# VermogensPrint.net
KiCad netlist of a schematic drawn in Altium Designer
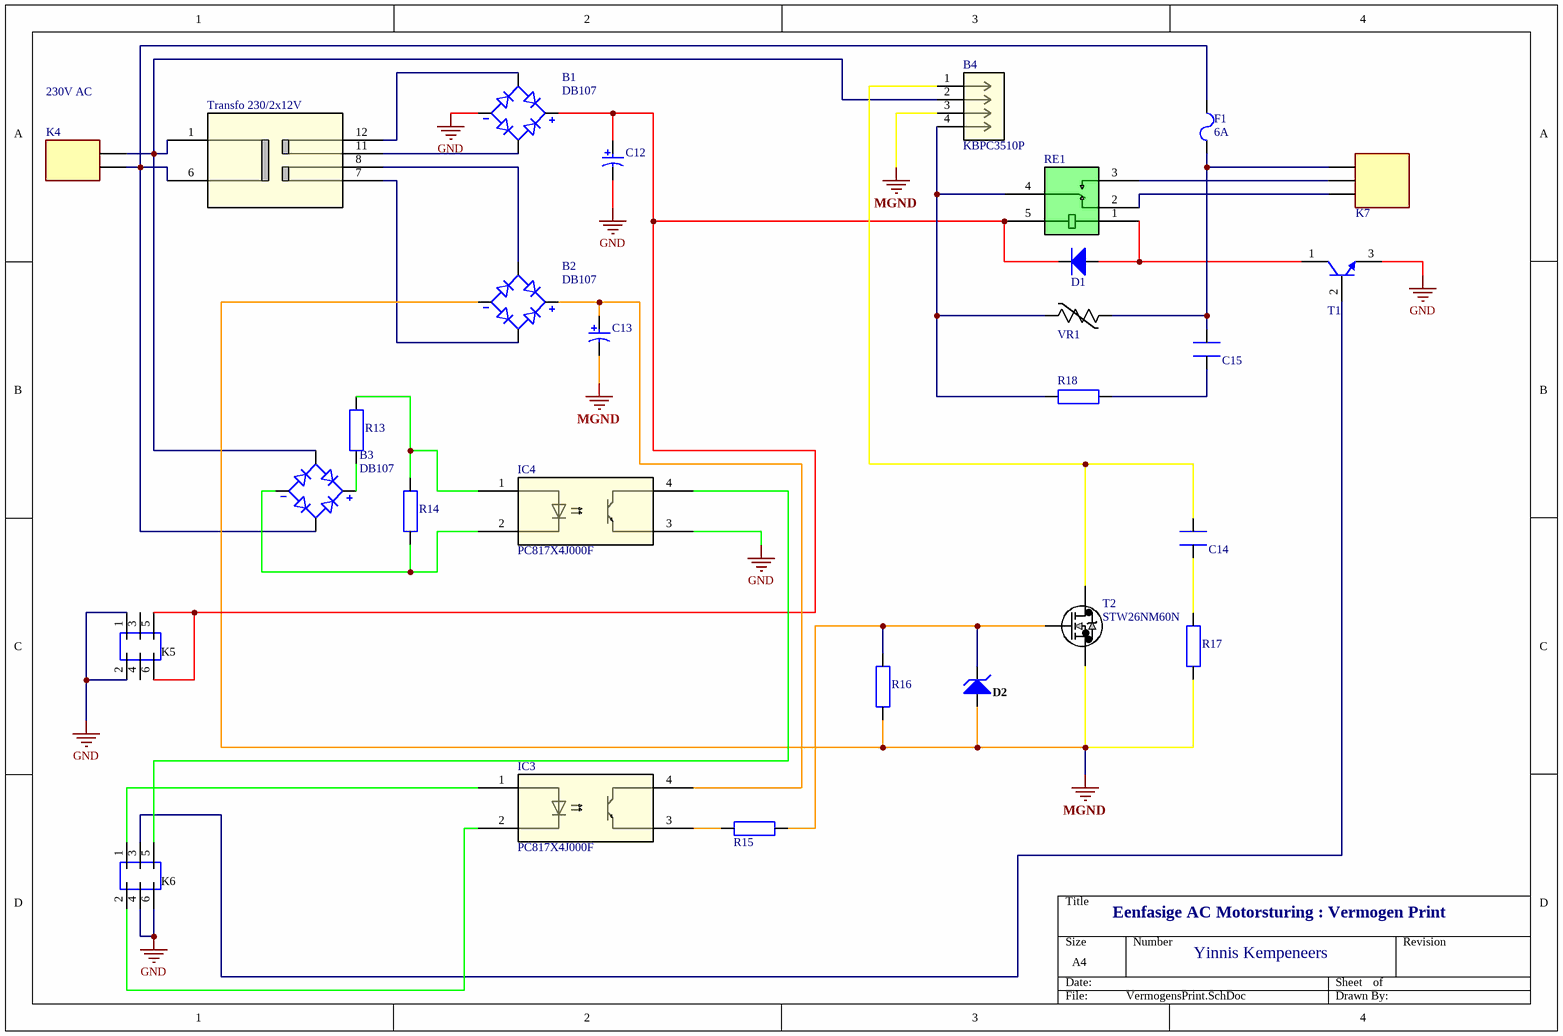
[diagram p0: VermogensPrint.SchDoc]

(export (version "E")
  (design (tool "Eeschema 10.0.6"))
  (components
    (comp (ref "B1")
      (value "DB107")
      (footprint "DB107")
      (libsource (lib "Schlib_Motorvermogen") (part "DB107"))
    )
    (comp (ref "B2")
      (value "DB107")
      (footprint "DB107")
      (libsource (lib "Schlib_Motorvermogen") (part "DB107"))
    )
    (comp (ref "B3")
      (value "DB107")
      (footprint "DB107")
      (libsource (lib "Schlib_Motorvermogen") (part "DB107"))
    )
    (comp (ref "B4")
      (value "KBPC3510P")
      (footprint "KBPC3510")
      (description "No Description Available")
      (libsource (lib "Schlib_Motorvermogen") (part "KBPC3510P"))
    )
    (comp (ref "C12")
      (value "470µF")
      (footprint "Capacitor")
      (description "Capacitor 470µF 50V")
      (libsource (lib "Schlib_Motorvermogen") (part "470µF"))
    )
    (comp (ref "C13")
      (value "470µF")
      (footprint "Capacitor")
      (description "Capacitor 470µF 50V")
      (libsource (lib "Schlib_Motorvermogen") (part "470µF"))
    )
    (comp (ref "C14")
      (value "Capacitor 0.22µF 630V")
      (footprint "0.22µF")
      (libsource (lib "Schlib_Motorvermogen") (part "Capacitor 0.22µF 630V"))
    )
    (comp (ref "C15")
      (value "0.22µF")
      (footprint "0.22µF")
      (description "Capacitor 0.22µF 630V")
      (libsource (lib "Schlib_Motorvermogen") (part "Capacitor 0.22µF 630V"))
    )
    (comp (ref "D1")
      (value "1N4007-T")
      (footprint "1N4007-T")
      (description "1.0 A Rectifier, 8 pF, 1000 V, -65 to 150 degC, 2-Pin DO-41 Plastic, RoHS, Tape and Reel")
      (fields (field (name "MANUFACTURER") "Diodes Inc"))
      (libsource (lib "Schlib_Motorvermogen") (part "1N4007-T"))
    )
    (comp (ref "D2")
      (value "1N4742A")
      (footprint "1N4742A")
      (description "Zener Diode, 12V, 1W, 5%, -65 to 200 degC, 2-Pin DO-41, Body 2.72 x 5.2 mm, RoHS")
      (fields (field (name "TOLERANCE") "5%") (field (name "MANUFACTURER") "Fairchild Semiconductor"))
      (libsource (lib "Schlib_Motorvermogen") (part "1N4742A"))
    )
    (comp (ref "F1")
      (value "6A")
      (footprint "FUSE")
      (description "No Description Available")
      (libsource (lib "Schlib_Motorvermogen") (part "Fuse"))
    )
    (comp (ref "IC3")
      (value "PC817X4J000F")
      (footprint "PC817X4J000F")
      (description "OptoCoupler")
      (libsource (lib "Schlib_Motorvermogen") (part "PC817X4J000F"))
    )
    (comp (ref "IC4")
      (value "PC817X4J000F")
      (footprint "PC817X4J000F")
      (description "OptoCoupler")
      (libsource (lib "Schlib_Motorvermogen") (part "PC817X4J000F"))
    )
    (comp (ref "K4")
      (value "~")
      (footprint "2-Polige Connector")
      (description "2~24 Poles, Screw Type, Horizontal, 7.62 Pitch, 26~10 (AWG), Terminal Block Connector")
      (fields (field (name "MP") "TB005-762-02BE") (field (name "MF") "CUI Devices"))
      (libsource (lib "Schlib_Motorvermogen") (part "2-Polige Connector"))
    )
    (comp (ref "K5")
      (value "TSW-103-08-L-D")
      (footprint "Pin3x2")
      (description "Male Header, Pitch 2.54 mm, 2 x 3 Position,  8.9 x 15.22 x 11.95 mm")
      (fields (field (name "MANUFACTURER") "Samtec"))
      (libsource (lib "Schlib_Motorvermogen") (part "Connector3x2"))
    )
    (comp (ref "K6")
      (value "TSW-103-08-L-D")
      (footprint "Pin3x2")
      (description "Male Header, Pitch 2.54 mm, 2 x 3 Position,  8.9 x 15.22 x 11.95 mm")
      (fields (field (name "MANUFACTURER") "Samtec"))
      (libsource (lib "Schlib_Motorvermogen") (part "Connector3x2"))
    )
    (comp (ref "K7")
      (value "3-Polige Connetor")
      (footprint "3-Polige Connector")
      (fields (field (name "MP") "TB005-762-03BE"))
      (libsource (lib "Schlib_Motorvermogen") (part "3-Polige Connetor"))
    )
    (comp (ref "R13")
      (value "47K 3W")
      (footprint "47K 3W")
      (libsource (lib "Schlib_Motorvermogen") (part "47K 3W"))
    )
    (comp (ref "R14")
      (value "10K 2W")
      (footprint "Resistor")
      (libsource (lib "Schlib_Motorvermogen") (part "Resistor 250mW"))
    )
    (comp (ref "R15")
      (value "1K")
      (footprint "Resistor")
      (libsource (lib "Schlib_Motorvermogen") (part "Resistor 250mW"))
    )
    (comp (ref "R16")
      (value "10K")
      (footprint "Resistor")
      (libsource (lib "Schlib_Motorvermogen") (part "Resistor 250mW"))
    )
    (comp (ref "R17")
      (value "2K2 2W")
      (footprint "2K2 2W")
      (libsource (lib "Schlib_Motorvermogen") (part "2K2 2W"))
    )
    (comp (ref "R18")
      (value "560E 5W")
      (footprint "560Ohm 5W")
      (description "Resistor, 560 Ohm, ± 5%, 5 W, Axial Leaded, Wirewound, General Purpose")
      (fields (field (name "TOLERANCE") "5%"))
      (libsource (lib "Schlib_Motorvermogen") (part "560ohm5W"))
    )
    (comp (ref "RE1")
      (value "G2R-14 DC12")
      (footprint "RELAY_G2R-14_OMR")
      (description "No Description Available")
      (libsource (lib "Schlib_Motorvermogen") (part "G2R-14 DC12"))
    )
    (comp (ref "T1")
      (value "BC547B")
      (footprint "Transistor")
      (description "Amplifier Transistor, NPN Silicon, 3-Pin TO-92, Bulk Box")
      (fields (field (name "MANUFACTURER") "On Semiconductor"))
      (libsource (lib "Schlib_Motorvermogen") (part "BC547B"))
    )
    (comp (ref "T2")
      (value "STW26NM60N")
      (footprint "TO-247_STM")
      (description "No Description Available")
      (libsource (lib "Schlib_Motorvermogen") (part "STW26NM60N"))
    )
    (comp (ref "Transfo 230/2x12V")
      (value "T1")
      (footprint "T1")
      (description "No Description Available")
      (libsource (lib "Schlib_Motorvermogen") (part "T1"))
    )
    (comp (ref "VR1")
      (value "V25S275P")
      (footprint "VRES_V25S385P_LTF")
      (description "No Description Available")
      (libsource (lib "Schlib_Motorvermogen") (part "V25S385P"))
    )
  )
  (nets
    (net (code "1") (name "GND") (class "Default")
      (node (ref "B1") (pin "2") (pinfunction "NEG_2") (pintype "passive"))
      (node (ref "C12") (pin "2") (pinfunction "2_2") (pintype "passive"))
      (node (ref "IC4") (pin "3") (pinfunction "3_3") (pintype "passive"))
      (node (ref "K5") (pin "1") (pinfunction "1_1") (pintype "passive"))
      (node (ref "K5") (pin "2") (pinfunction "2_2") (pintype "passive"))
      (node (ref "K6") (pin "4") (pinfunction "4_4") (pintype "passive"))
      (node (ref "K6") (pin "6") (pinfunction "6_6") (pintype "passive"))
      (node (ref "T1") (pin "3") (pinfunction "E_3") (pintype "passive"))
    )
    (net (code "2") (name "MGND") (class "Default")
      (node (ref "B2") (pin "2") (pinfunction "NEG_2") (pintype "passive"))
      (node (ref "B4") (pin "3") (pinfunction "3_3") (pintype "passive"))
      (node (ref "C13") (pin "2") (pinfunction "2_2") (pintype "passive"))
      (node (ref "D2") (pin "1") (pinfunction "A_1") (pintype "passive"))
      (node (ref "R16") (pin "1") (pinfunction "1_1") (pintype "passive"))
      (node (ref "R17") (pin "1") (pinfunction "1_1") (pintype "passive"))
      (node (ref "T2") (pin "3") (pinfunction "3_3") (pintype "passive"))
    )
    (net (code "3") (name "Net-(B1-AC1)") (class "Default")
      (node (ref "B1") (pin "3") (pinfunction "AC1_3") (pintype "passive"))
      (node (ref "Transfo 230/2x12V") (pin "11") (pinfunction "11_11") (pintype "passive"))
    )
    (net (code "4") (name "Net-(B1-AC2)") (class "Default")
      (node (ref "B1") (pin "4") (pinfunction "AC2_4") (pintype "passive"))
      (node (ref "Transfo 230/2x12V") (pin "12") (pinfunction "12_12") (pintype "passive"))
    )
    (net (code "5") (name "Net-(B1-POS)") (class "Default")
      (node (ref "B1") (pin "1") (pinfunction "POS_1") (pintype "passive"))
      (node (ref "C12") (pin "1") (pinfunction "1_1") (pintype "passive"))
      (node (ref "D1") (pin "2") (pinfunction "K_2") (pintype "passive"))
      (node (ref "K5") (pin "5") (pinfunction "5_5") (pintype "passive"))
      (node (ref "K5") (pin "6") (pinfunction "6_6") (pintype "passive"))
      (node (ref "RE1") (pin "5") (pinfunction "5_5") (pintype "passive"))
    )
    (net (code "6") (name "Net-(B2-AC1)") (class "Default")
      (node (ref "B2") (pin "3") (pinfunction "AC1_3") (pintype "passive"))
      (node (ref "Transfo 230/2x12V") (pin "7") (pinfunction "7_7") (pintype "passive"))
    )
    (net (code "7") (name "Net-(B2-AC2)") (class "Default")
      (node (ref "B2") (pin "4") (pinfunction "AC2_4") (pintype "passive"))
      (node (ref "Transfo 230/2x12V") (pin "8") (pinfunction "8_8") (pintype "passive"))
    )
    (net (code "8") (name "Net-(B2-POS)") (class "Default")
      (node (ref "B2") (pin "1") (pinfunction "POS_1") (pintype "passive"))
      (node (ref "C13") (pin "1") (pinfunction "1_1") (pintype "passive"))
      (node (ref "IC3") (pin "4") (pinfunction "4_4") (pintype "passive"))
    )
    (net (code "9") (name "Net-(B3-AC1)") (class "Default")
      (node (ref "B3") (pin "3") (pinfunction "AC1_3") (pintype "passive"))
      (node (ref "F1") (pin "2") (pinfunction "2_2") (pintype "passive"))
      (node (ref "K4") (pin "1") (pinfunction "1_1") (pintype "passive"))
      (node (ref "Transfo 230/2x12V") (pin "6") (pinfunction "6_6") (pintype "passive"))
    )
    (net (code "10") (name "Net-(B3-AC2)") (class "Default")
      (node (ref "B3") (pin "4") (pinfunction "AC2_4") (pintype "passive"))
      (node (ref "B4") (pin "2") (pinfunction "2_2") (pintype "passive"))
      (node (ref "K4") (pin "2") (pinfunction "2_2") (pintype "passive"))
      (node (ref "Transfo 230/2x12V") (pin "1") (pinfunction "1_1") (pintype "passive"))
    )
    (net (code "11") (name "Net-(B3-NEG)") (class "Default")
      (node (ref "B3") (pin "2") (pinfunction "NEG_2") (pintype "passive"))
      (node (ref "IC4") (pin "2") (pinfunction "2_2") (pintype "passive"))
      (node (ref "R14") (pin "1") (pinfunction "1_1") (pintype "passive"))
    )
    (net (code "12") (name "Net-(B3-POS)") (class "Default")
      (node (ref "B3") (pin "1") (pinfunction "POS_1") (pintype "passive"))
      (node (ref "R13") (pin "2") (pinfunction "2_2") (pintype "passive"))
    )
    (net (code "13") (name "Net-(B4-Pad1)") (class "Default")
      (node (ref "B4") (pin "1") (pinfunction "1_1") (pintype "passive"))
      (node (ref "C14") (pin "1") (pinfunction "1_1") (pintype "passive"))
      (node (ref "T2") (pin "2") (pinfunction "2_2") (pintype "passive"))
    )
    (net (code "14") (name "Net-(B4-Pad4)") (class "Default")
      (node (ref "B4") (pin "4") (pinfunction "4_4") (pintype "passive"))
      (node (ref "R18") (pin "1") (pinfunction "1_1") (pintype "passive"))
      (node (ref "RE1") (pin "4") (pinfunction "4_4") (pintype "passive"))
      (node (ref "VR1") (pin "2") (pinfunction "2_2") (pintype "passive"))
    )
    (net (code "15") (name "Net-(C14-Pad2)") (class "Default")
      (node (ref "C14") (pin "2") (pinfunction "2_2") (pintype "passive"))
      (node (ref "R17") (pin "2") (pinfunction "2_2") (pintype "passive"))
    )
    (net (code "16") (name "Net-(C15-Pad1)") (class "Default")
      (node (ref "C15") (pin "1") (pinfunction "1_1") (pintype "passive"))
      (node (ref "F1") (pin "1") (pinfunction "1_1") (pintype "passive"))
      (node (ref "K7") (pin "1") (pinfunction "1_1") (pintype "passive"))
      (node (ref "VR1") (pin "1") (pinfunction "1_1") (pintype "passive"))
    )
    (net (code "17") (name "Net-(C15-Pad2)") (class "Default")
      (node (ref "C15") (pin "2") (pinfunction "2_2") (pintype "passive"))
      (node (ref "R18") (pin "2") (pinfunction "2_2") (pintype "passive"))
    )
    (net (code "18") (name "Net-(D1-A)") (class "Default")
      (node (ref "D1") (pin "1") (pinfunction "A_1") (pintype "passive"))
      (node (ref "RE1") (pin "1") (pinfunction "1_1") (pintype "passive"))
      (node (ref "T1") (pin "1") (pinfunction "C_1") (pintype "passive"))
    )
    (net (code "19") (name "Net-(D2-K)") (class "Default")
      (node (ref "D2") (pin "2") (pinfunction "K_2") (pintype "passive"))
      (node (ref "R15") (pin "2") (pinfunction "2_2") (pintype "passive"))
      (node (ref "R16") (pin "2") (pinfunction "2_2") (pintype "passive"))
      (node (ref "T2") (pin "1") (pinfunction "1_1") (pintype "passive"))
    )
    (net (code "20") (name "Net-(IC3-Pad1)") (class "Default")
      (node (ref "IC3") (pin "1") (pinfunction "1_1") (pintype "passive"))
      (node (ref "K6") (pin "1") (pinfunction "1_1") (pintype "passive"))
    )
    (net (code "21") (name "Net-(IC3-Pad2)") (class "Default")
      (node (ref "IC3") (pin "2") (pinfunction "2_2") (pintype "passive"))
      (node (ref "K6") (pin "2") (pinfunction "2_2") (pintype "passive"))
    )
    (net (code "22") (name "Net-(IC3-Pad3)") (class "Default")
      (node (ref "IC3") (pin "3") (pinfunction "3_3") (pintype "passive"))
      (node (ref "R15") (pin "1") (pinfunction "1_1") (pintype "passive"))
    )
    (net (code "23") (name "Net-(IC4-Pad1)") (class "Default")
      (node (ref "IC4") (pin "1") (pinfunction "1_1") (pintype "passive"))
      (node (ref "R13") (pin "1") (pinfunction "1_1") (pintype "passive"))
      (node (ref "R14") (pin "2") (pinfunction "2_2") (pintype "passive"))
    )
    (net (code "24") (name "Net-(IC4-Pad4)") (class "Default")
      (node (ref "IC4") (pin "4") (pinfunction "4_4") (pintype "passive"))
      (node (ref "K6") (pin "5") (pinfunction "5_5") (pintype "passive"))
    )
    (net (code "25") (name "Net-(K7-Pad2)") (class "Default")
      (node (ref "K7") (pin "2") (pinfunction "2_2") (pintype "passive"))
      (node (ref "RE1") (pin "3") (pinfunction "3_3") (pintype "passive"))
    )
    (net (code "26") (name "Net-(K7-Pad3)") (class "Default")
      (node (ref "K7") (pin "3") (pinfunction "3_3") (pintype "passive"))
      (node (ref "RE1") (pin "2") (pinfunction "2_2") (pintype "passive"))
    )
    (net (code "27") (name "Net-(T1-B)") (class "Default")
      (node (ref "K6") (pin "3") (pinfunction "3_3") (pintype "passive"))
      (node (ref "T1") (pin "2") (pinfunction "B_2") (pintype "passive"))
    )
    (net (code "28") (name "unconnected-(K5-Pad3)") (class "Default")
      (node (ref "K5") (pin "3") (pinfunction "3_3") (pintype "passive"))
    )
    (net (code "29") (name "unconnected-(K5-Pad4)") (class "Default")
      (node (ref "K5") (pin "4") (pinfunction "4_4") (pintype "passive"))
    )
  )
)
